# Audio_Lights.net
KiCad netlist of a schematic drawn in EAGLE
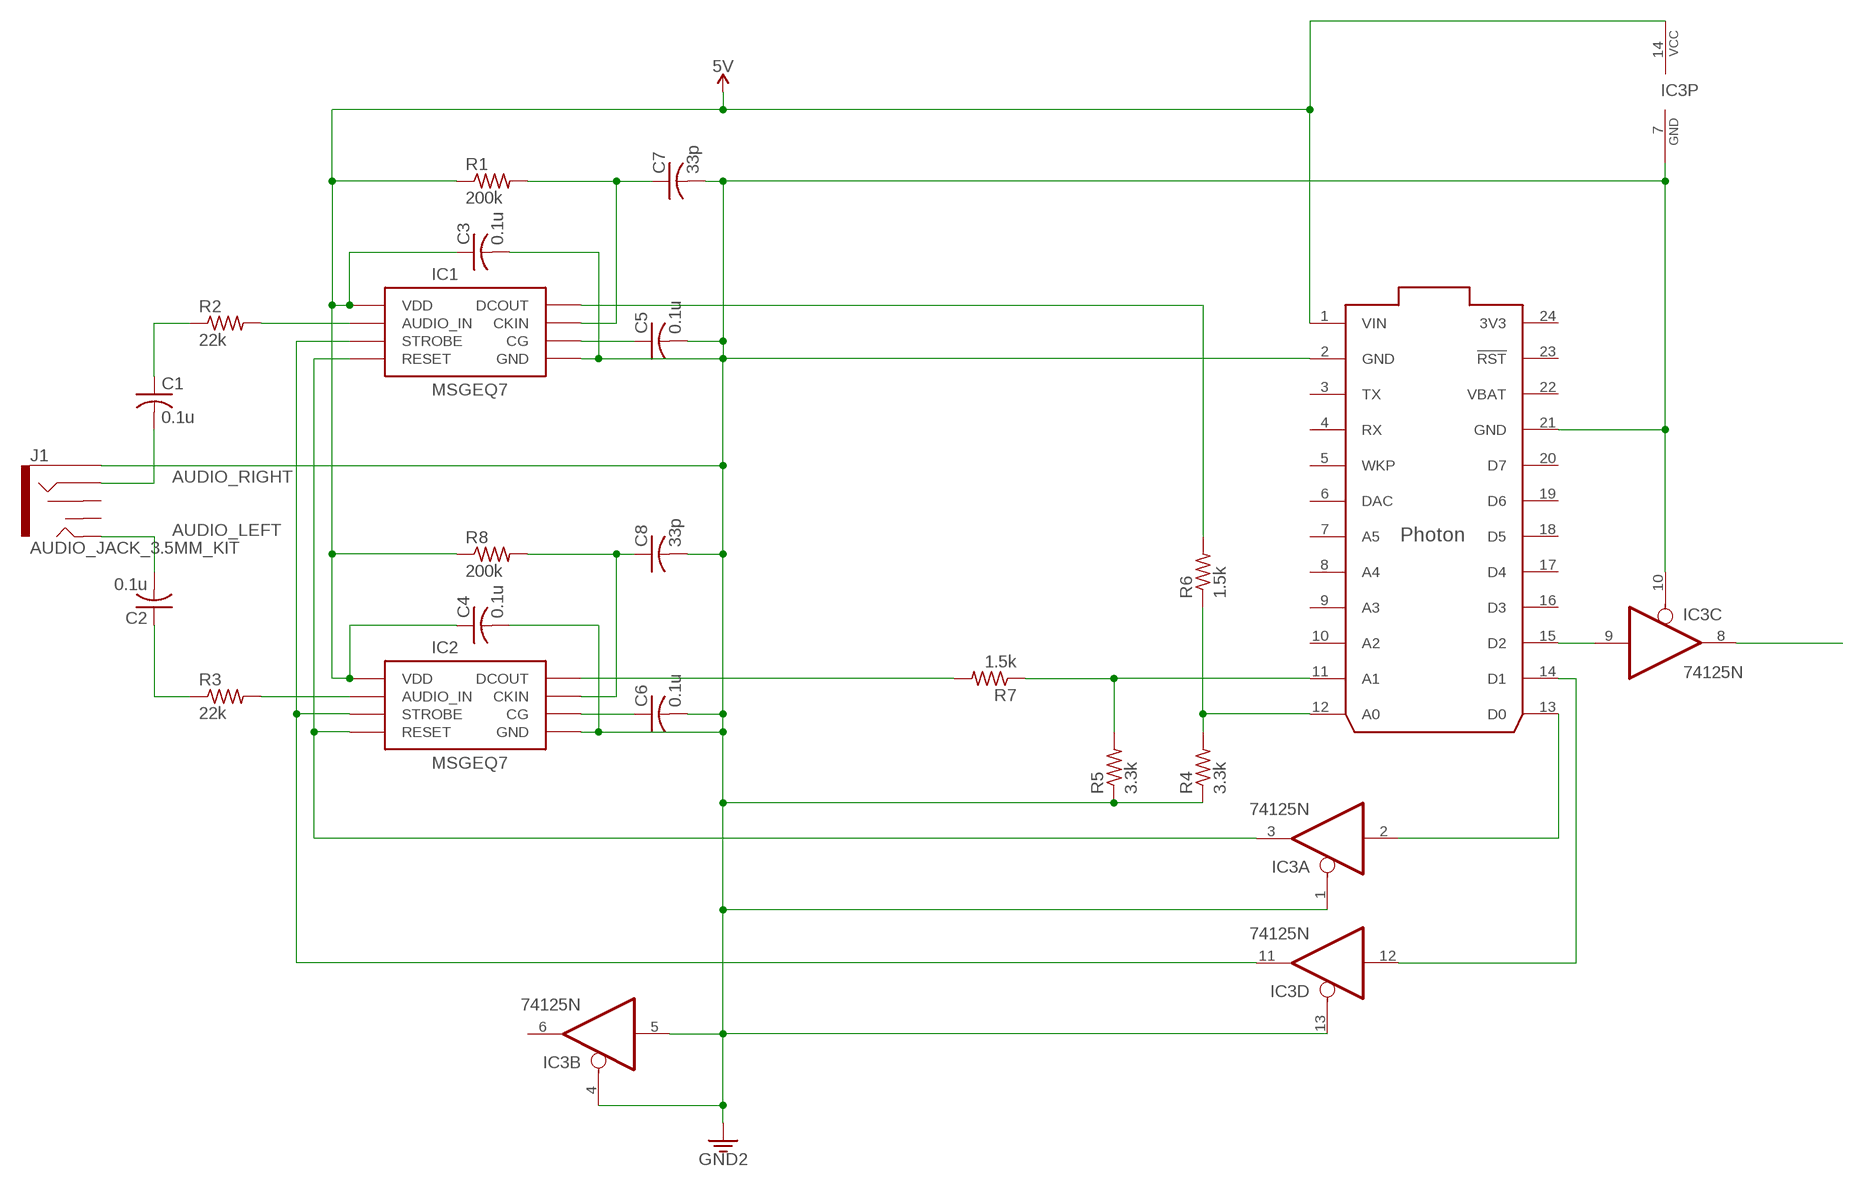
[diagram p0: schematic, sheet 1]

(export (version "E")
  (design (tool "Eeschema 10.0.6"))
  (components
    (comp (ref "C1")
      (value "0.1u")
      (footprint "eagle-import:C025-024X044")
      (libsource (lib "eagle-import") (part "C-US025-024X044"))
    )
    (comp (ref "C2")
      (value "0.1u")
      (footprint "eagle-import:C025-024X044")
      (libsource (lib "eagle-import") (part "C-US025-024X044"))
    )
    (comp (ref "C3")
      (value "0.1u")
      (footprint "eagle-import:C025-024X044")
      (libsource (lib "eagle-import") (part "C-US025-024X044"))
    )
    (comp (ref "C4")
      (value "0.1u")
      (footprint "eagle-import:C025-024X044")
      (libsource (lib "eagle-import") (part "C-US025-024X044"))
    )
    (comp (ref "C5")
      (value "0.1u")
      (footprint "eagle-import:C025-024X044")
      (libsource (lib "eagle-import") (part "C-US025-024X044"))
    )
    (comp (ref "C6")
      (value "0.1u")
      (footprint "eagle-import:C025-024X044")
      (libsource (lib "eagle-import") (part "C-US025-024X044"))
    )
    (comp (ref "C7")
      (value "33p")
      (footprint "eagle-import:C050-045X075")
      (libsource (lib "eagle-import") (part "C-US050-045X075"))
    )
    (comp (ref "C8")
      (value "33p")
      (footprint "eagle-import:C050-045X075")
      (libsource (lib "eagle-import") (part "C-US050-045X075"))
    )
    (comp (ref "IC1")
      (value "MSGEQ7P")
      (footprint "eagle-import:DIP08")
      (libsource (lib "eagle-import") (part "MSGEQ7DIL"))
    )
    (comp (ref "IC2")
      (value "MSGEQ7P")
      (footprint "eagle-import:DIP08")
      (libsource (lib "eagle-import") (part "MSGEQ7DIL"))
    )
    (comp (ref "IC3")
      (value "74125N")
      (footprint "eagle-import:DIL14")
      (libsource (lib "eagle-import") (part "74125N"))
    )
    (comp (ref "J1")
      (value "AUDIO_JACK_3.5MM_KIT")
      (footprint "eagle-import:AUDIO-JACK-KIT")
      (libsource (lib "eagle-import") (part "AUDIO_JACK_3.5MM_KIT"))
    )
    (comp (ref "R1")
      (value "200k")
      (footprint "eagle-import:0204_7")
      (libsource (lib "eagle-import") (part "R-US_0204/7"))
    )
    (comp (ref "R2")
      (value "22k")
      (footprint "eagle-import:0204_7")
      (libsource (lib "eagle-import") (part "R-US_0204/7"))
    )
    (comp (ref "R3")
      (value "22k")
      (footprint "eagle-import:0204_7")
      (libsource (lib "eagle-import") (part "R-US_0204/7"))
    )
    (comp (ref "R4")
      (value "3.3k")
      (footprint "eagle-import:0204_5")
      (libsource (lib "eagle-import") (part "R-US_0204/5"))
    )
    (comp (ref "R5")
      (value "3.3k")
      (footprint "eagle-import:0204_5")
      (libsource (lib "eagle-import") (part "R-US_0204/5"))
    )
    (comp (ref "R6")
      (value "1.5k")
      (footprint "eagle-import:0204_5")
      (libsource (lib "eagle-import") (part "R-US_0204/5"))
    )
    (comp (ref "R7")
      (value "1.5k")
      (footprint "eagle-import:0204_5")
      (libsource (lib "eagle-import") (part "R-US_0204/5"))
    )
    (comp (ref "R8")
      (value "200k")
      (footprint "eagle-import:0204_7")
      (libsource (lib "eagle-import") (part "R-US_0204/7"))
    )
    (comp (ref "U$1")
      (value "PHOTON_WITH_HEADERS")
      (footprint "eagle-import:PHOTON")
      (libsource (lib "eagle-import") (part "PHOTON_WITH_HEADERS"))
    )
  )
  (nets
    (net (code "1") (name "/3V3") (class "Default")
      (node (ref "U$1") (pin "24") (pinfunction "3V3_24") (pintype "power_in"))
    )
    (net (code "2") (name "/AUDIO_LEFT") (class "Default")
      (node (ref "C2") (pin "2") (pinfunction "2_2") (pintype "passive"))
      (node (ref "J1") (pin "TIP") (pinfunction "TIP_TIP") (pintype "bidirectional"))
    )
    (net (code "3") (name "/AUDIO_RIGHT") (class "Default")
      (node (ref "C1") (pin "2") (pinfunction "2_2") (pintype "passive"))
      (node (ref "J1") (pin "RING") (pinfunction "RING_RING") (pintype "bidirectional"))
    )
    (net (code "4") (name "/VBAT") (class "Default")
      (node (ref "U$1") (pin "22") (pinfunction "VBAT_22") (pintype "power_in"))
    )
    (net (code "5") (name "5V") (class "Default")
      (node (ref "C3") (pin "1") (pinfunction "1_1") (pintype "passive"))
      (node (ref "C4") (pin "1") (pinfunction "1_1") (pintype "passive"))
      (node (ref "IC1") (pin "1") (pinfunction "VDD_1") (pintype "input"))
      (node (ref "IC2") (pin "1") (pinfunction "VDD_1") (pintype "input"))
      (node (ref "IC3") (pin "14") (pinfunction "VCC_14") (pintype "power_in"))
      (node (ref "R1") (pin "1") (pinfunction "1_1") (pintype "passive"))
      (node (ref "R8") (pin "1") (pinfunction "1_1") (pintype "passive"))
      (node (ref "U$1") (pin "1") (pinfunction "VIN_1") (pintype "power_in"))
    )
    (net (code "6") (name "GND2") (class "Default")
      (node (ref "C3") (pin "2") (pinfunction "2_2") (pintype "passive"))
      (node (ref "C4") (pin "2") (pinfunction "2_2") (pintype "passive"))
      (node (ref "C5") (pin "2") (pinfunction "2_2") (pintype "passive"))
      (node (ref "C6") (pin "2") (pinfunction "2_2") (pintype "passive"))
      (node (ref "C7") (pin "2") (pinfunction "2_2") (pintype "passive"))
      (node (ref "C8") (pin "2") (pinfunction "2_2") (pintype "passive"))
      (node (ref "IC1") (pin "2") (pinfunction "GND_2") (pintype "bidirectional"))
      (node (ref "IC2") (pin "2") (pinfunction "GND_2") (pintype "bidirectional"))
      (node (ref "IC3") (pin "1") (pinfunction "OE_1") (pintype "input"))
      (node (ref "IC3") (pin "10") (pinfunction "OE_10") (pintype "input"))
      (node (ref "IC3") (pin "13") (pinfunction "OE_13") (pintype "input"))
      (node (ref "IC3") (pin "4") (pinfunction "OE_4") (pintype "input"))
      (node (ref "IC3") (pin "5") (pinfunction "I_5") (pintype "input"))
      (node (ref "IC3") (pin "7") (pinfunction "GND_7") (pintype "power_in"))
      (node (ref "J1") (pin "SLEEVE") (pinfunction "SLEEVE_SLEEVE") (pintype "bidirectional"))
      (node (ref "R4") (pin "1") (pinfunction "1_1") (pintype "passive"))
      (node (ref "R5") (pin "1") (pinfunction "1_1") (pintype "passive"))
      (node (ref "U$1") (pin "2") (pinfunction "GND_2") (pintype "power_in"))
      (node (ref "U$1") (pin "21") (pinfunction "GND_21") (pintype "power_in"))
    )
    (net (code "7") (name "Net-(C1-Pad1)") (class "Default")
      (node (ref "C1") (pin "1") (pinfunction "1_1") (pintype "passive"))
      (node (ref "R2") (pin "1") (pinfunction "1_1") (pintype "passive"))
    )
    (net (code "8") (name "Net-(C2-Pad1)") (class "Default")
      (node (ref "C2") (pin "1") (pinfunction "1_1") (pintype "passive"))
      (node (ref "R3") (pin "1") (pinfunction "1_1") (pintype "passive"))
    )
    (net (code "9") (name "Net-(IC1-AUDIO_IN)") (class "Default")
      (node (ref "IC1") (pin "5") (pinfunction "AUDIO_IN_5") (pintype "input"))
      (node (ref "R2") (pin "2") (pinfunction "2_2") (pintype "passive"))
    )
    (net (code "10") (name "Net-(IC1-CG)") (class "Default")
      (node (ref "C5") (pin "1") (pinfunction "1_1") (pintype "passive"))
      (node (ref "IC1") (pin "6") (pinfunction "CG_6") (pintype "bidirectional"))
    )
    (net (code "11") (name "Net-(IC1-CKIN)") (class "Default")
      (node (ref "C7") (pin "1") (pinfunction "1_1") (pintype "passive"))
      (node (ref "IC1") (pin "8") (pinfunction "CKIN_8") (pintype "bidirectional"))
      (node (ref "R1") (pin "2") (pinfunction "2_2") (pintype "passive"))
    )
    (net (code "12") (name "Net-(IC1-DCOUT)") (class "Default")
      (node (ref "IC1") (pin "3") (pinfunction "DCOUT_3") (pintype "bidirectional"))
      (node (ref "R6") (pin "2") (pinfunction "2_2") (pintype "passive"))
    )
    (net (code "13") (name "Net-(IC1-RESET)") (class "Default")
      (node (ref "IC1") (pin "7") (pinfunction "RESET_7") (pintype "input"))
      (node (ref "IC2") (pin "7") (pinfunction "RESET_7") (pintype "input"))
      (node (ref "IC3") (pin "3") (pinfunction "O_3") (pintype "tri_state"))
    )
    (net (code "14") (name "Net-(IC1-STROBE)") (class "Default")
      (node (ref "IC1") (pin "4") (pinfunction "STROBE_4") (pintype "input"))
      (node (ref "IC2") (pin "4") (pinfunction "STROBE_4") (pintype "input"))
      (node (ref "IC3") (pin "11") (pinfunction "O_11") (pintype "tri_state"))
    )
    (net (code "15") (name "Net-(IC2-AUDIO_IN)") (class "Default")
      (node (ref "IC2") (pin "5") (pinfunction "AUDIO_IN_5") (pintype "input"))
      (node (ref "R3") (pin "2") (pinfunction "2_2") (pintype "passive"))
    )
    (net (code "16") (name "Net-(IC2-CG)") (class "Default")
      (node (ref "C6") (pin "1") (pinfunction "1_1") (pintype "passive"))
      (node (ref "IC2") (pin "6") (pinfunction "CG_6") (pintype "bidirectional"))
    )
    (net (code "17") (name "Net-(IC2-CKIN)") (class "Default")
      (node (ref "C8") (pin "1") (pinfunction "1_1") (pintype "passive"))
      (node (ref "IC2") (pin "8") (pinfunction "CKIN_8") (pintype "bidirectional"))
      (node (ref "R8") (pin "2") (pinfunction "2_2") (pintype "passive"))
    )
    (net (code "18") (name "Net-(IC2-DCOUT)") (class "Default")
      (node (ref "IC2") (pin "3") (pinfunction "DCOUT_3") (pintype "bidirectional"))
      (node (ref "R7") (pin "2") (pinfunction "2_2") (pintype "passive"))
    )
    (net (code "19") (name "Net-(IC3A-I)") (class "Default")
      (node (ref "IC3") (pin "2") (pinfunction "I_2") (pintype "input"))
      (node (ref "U$1") (pin "13") (pinfunction "D0_13") (pintype "bidirectional"))
    )
    (net (code "20") (name "Net-(IC3C-I)") (class "Default")
      (node (ref "IC3") (pin "9") (pinfunction "I_9") (pintype "input"))
      (node (ref "U$1") (pin "15") (pinfunction "D2_15") (pintype "bidirectional"))
    )
    (net (code "21") (name "Net-(IC3D-I)") (class "Default")
      (node (ref "IC3") (pin "12") (pinfunction "I_12") (pintype "input"))
      (node (ref "U$1") (pin "14") (pinfunction "D1_14") (pintype "bidirectional"))
    )
    (net (code "22") (name "Net-(U$1-A0)") (class "Default")
      (node (ref "R4") (pin "2") (pinfunction "2_2") (pintype "passive"))
      (node (ref "R6") (pin "1") (pinfunction "1_1") (pintype "passive"))
      (node (ref "U$1") (pin "12") (pinfunction "A0_12") (pintype "bidirectional"))
    )
    (net (code "23") (name "Net-(U$1-A1)") (class "Default")
      (node (ref "R5") (pin "2") (pinfunction "2_2") (pintype "passive"))
      (node (ref "R7") (pin "1") (pinfunction "1_1") (pintype "passive"))
      (node (ref "U$1") (pin "11") (pinfunction "A1_11") (pintype "bidirectional"))
    )
    (net (code "24") (name "unconnected-(IC3B-O-Pad6)") (class "Default")
      (node (ref "IC3") (pin "6") (pinfunction "O_6") (pintype "tri_state"))
    )
    (net (code "25") (name "unconnected-(IC3C-O-Pad8)") (class "Default")
      (node (ref "IC3") (pin "8") (pinfunction "O_8") (pintype "tri_state"))
    )
    (net (code "26") (name "unconnected-(J1-PadRSH)") (class "Default")
      (node (ref "J1") (pin "RSH") (pinfunction "RSH_RSH") (pintype "bidirectional"))
    )
    (net (code "27") (name "unconnected-(J1-PadTSH)") (class "Default")
      (node (ref "J1") (pin "TSH") (pinfunction "TSH_TSH") (pintype "bidirectional"))
    )
    (net (code "28") (name "unconnected-(U$1-A2-Pad10)") (class "Default")
      (node (ref "U$1") (pin "10") (pinfunction "A2_10") (pintype "bidirectional"))
    )
    (net (code "29") (name "unconnected-(U$1-A3-Pad9)") (class "Default")
      (node (ref "U$1") (pin "9") (pinfunction "A3_9") (pintype "bidirectional"))
    )
    (net (code "30") (name "unconnected-(U$1-A4-Pad8)") (class "Default")
      (node (ref "U$1") (pin "8") (pinfunction "A4_8") (pintype "bidirectional"))
    )
    (net (code "31") (name "unconnected-(U$1-A5-Pad7)") (class "Default")
      (node (ref "U$1") (pin "7") (pinfunction "A5_7") (pintype "bidirectional"))
    )
    (net (code "32") (name "unconnected-(U$1-D3-Pad16)") (class "Default")
      (node (ref "U$1") (pin "16") (pinfunction "D3_16") (pintype "bidirectional"))
    )
    (net (code "33") (name "unconnected-(U$1-D4-Pad17)") (class "Default")
      (node (ref "U$1") (pin "17") (pinfunction "D4_17") (pintype "bidirectional"))
    )
    (net (code "34") (name "unconnected-(U$1-D5-Pad18)") (class "Default")
      (node (ref "U$1") (pin "18") (pinfunction "D5_18") (pintype "bidirectional"))
    )
    (net (code "35") (name "unconnected-(U$1-D6-Pad19)") (class "Default")
      (node (ref "U$1") (pin "19") (pinfunction "D6_19") (pintype "bidirectional"))
    )
    (net (code "36") (name "unconnected-(U$1-D7-Pad20)") (class "Default")
      (node (ref "U$1") (pin "20") (pinfunction "D7_20") (pintype "bidirectional"))
    )
    (net (code "37") (name "unconnected-(U$1-DAC-Pad6)") (class "Default")
      (node (ref "U$1") (pin "6") (pinfunction "DAC_6") (pintype "bidirectional"))
    )
    (net (code "38") (name "unconnected-(U$1-RX-Pad4)") (class "Default")
      (node (ref "U$1") (pin "4") (pinfunction "RX_4") (pintype "bidirectional"))
    )
    (net (code "39") (name "unconnected-(U$1-TX-Pad3)") (class "Default")
      (node (ref "U$1") (pin "3") (pinfunction "TX_3") (pintype "bidirectional"))
    )
    (net (code "40") (name "unconnected-(U$1-WKP-Pad5)") (class "Default")
      (node (ref "U$1") (pin "5") (pinfunction "WKP_5") (pintype "bidirectional"))
    )
    (net (code "41") (name "unconnected-(U$1-~{RST}-Pad23)") (class "Default")
      (node (ref "U$1") (pin "23") (pinfunction "~{RST}_23") (pintype "bidirectional"))
    )
  )
)
